# 05_LMS7002M_RF1.net
KiCad netlist of a schematic drawn in Altium Designer
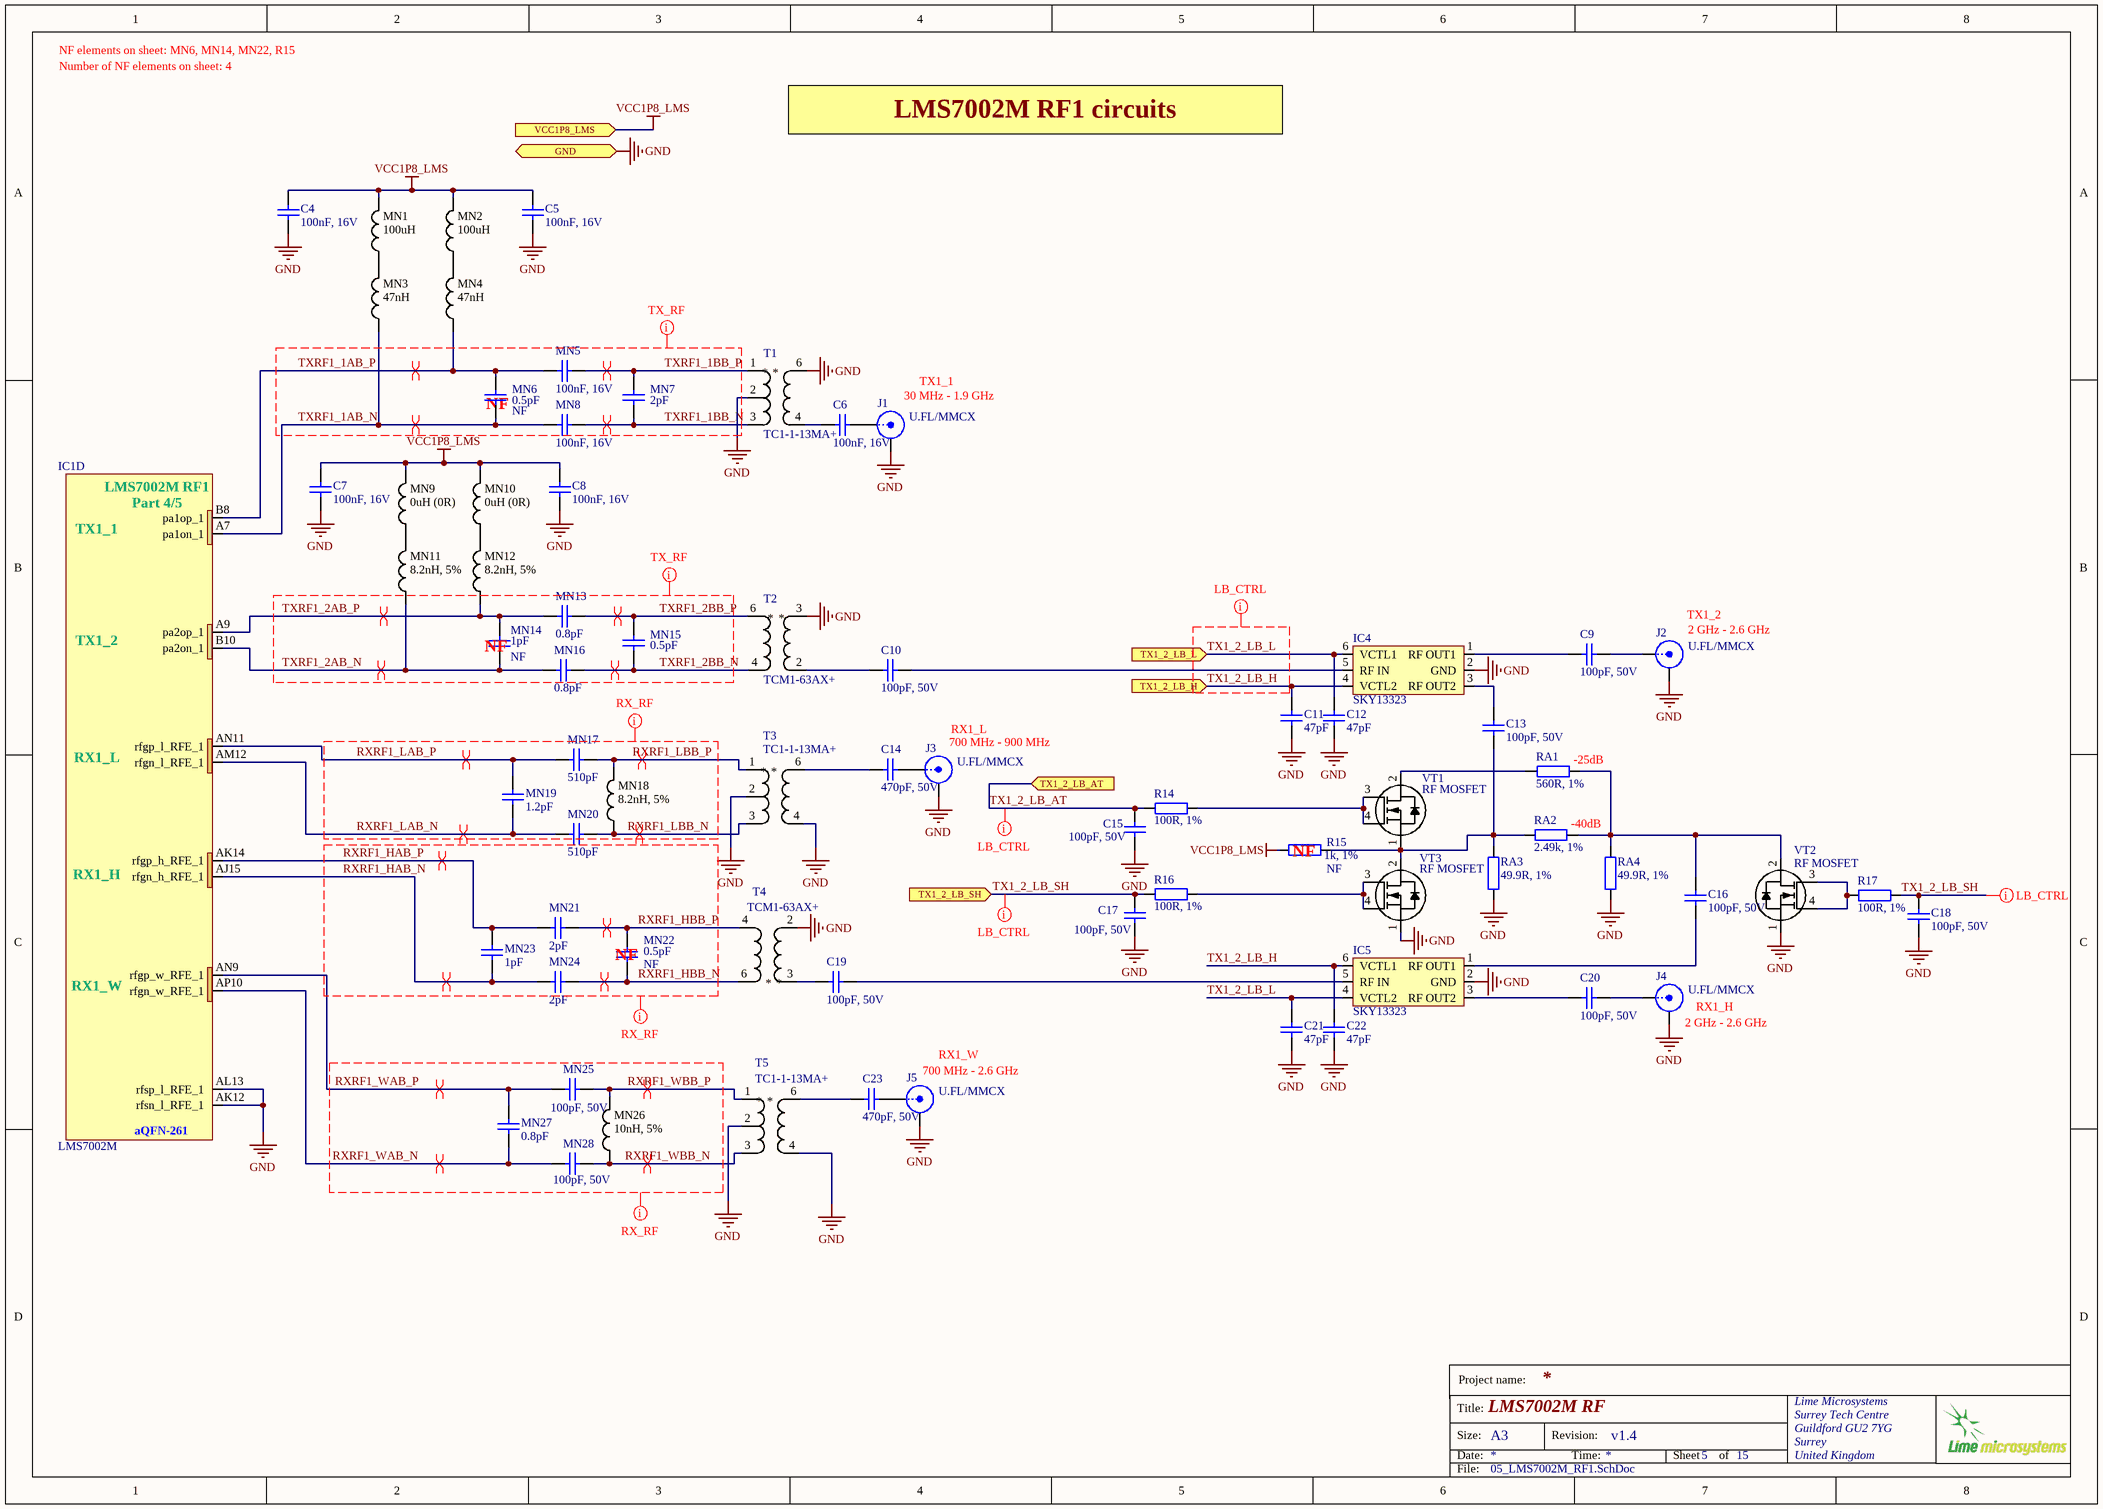
[diagram p0: 05_LMS7002M_RF1.SchDoc]

(export (version "E")
  (design (tool "Eeschema 10.0.6"))
  (components
    (comp (ref "C4")
      (value "100nF, 16V")
      (footprint "CAP0402")
      (fields
        (field (name "MANUFACTURER") "Murata Electronics")
        (field (name "TOLERANCE") "10 %")
        (field (name "MANUFACTURER PART NUMBER") "GRM155R71C104KA88D")
      )
      (libsource (lib "LimeMicroAltiumLib_schLib") (part "Cap_0402"))
    )
    (comp (ref "C5")
      (value "100nF, 16V")
      (footprint "CAP0402")
      (fields
        (field (name "MANUFACTURER") "Murata Electronics")
        (field (name "TOLERANCE") "10 %")
        (field (name "MANUFACTURER PART NUMBER") "GRM155R71C104KA88D")
      )
      (libsource (lib "LimeMicroAltiumLib_schLib") (part "Cap_0402"))
    )
    (comp (ref "C6")
      (value "100nF, 16V")
      (footprint "CAP0402")
      (fields
        (field (name "MANUFACTURER") "Murata Electronics")
        (field (name "TOLERANCE") "10 %")
        (field (name "MANUFACTURER PART NUMBER") "GRM155R71C104KA88D")
      )
      (libsource (lib "LimeMicroAltiumLib_schLib") (part "Cap_0402"))
    )
    (comp (ref "C7")
      (value "100nF, 16V")
      (footprint "CAP0402")
      (fields
        (field (name "MANUFACTURER") "Murata Electronics")
        (field (name "TOLERANCE") "10 %")
        (field (name "MANUFACTURER PART NUMBER") "GRM155R71C104KA88D")
      )
      (libsource (lib "LimeMicroAltiumLib_schLib") (part "Cap_0402"))
    )
    (comp (ref "C8")
      (value "100nF, 16V")
      (footprint "CAP0402")
      (fields
        (field (name "MANUFACTURER") "Murata Electronics")
        (field (name "TOLERANCE") "10 %")
        (field (name "MANUFACTURER PART NUMBER") "GRM155R71C104KA88D")
      )
      (libsource (lib "LimeMicroAltiumLib_schLib") (part "Cap_0402"))
    )
    (comp (ref "C9")
      (value "100pF, 50V")
      (footprint "CAP0402")
      (fields (field (name "TOLERANCE") "±5%") (field (name "MANUFACTURER") "Yageo"))
      (libsource (lib "LimeMicroAltiumLib_schLib") (part "Cap_0402"))
    )
    (comp (ref "C10")
      (value "100pF, 50V")
      (footprint "CAP0402")
      (fields (field (name "TOLERANCE") "±5%") (field (name "MANUFACTURER") "Yageo"))
      (libsource (lib "LimeMicroAltiumLib_schLib") (part "Cap_0402"))
    )
    (comp (ref "C11")
      (value "47pF")
      (footprint "CAP0402")
      (fields (field (name "TOLERANCE") "±1%") (field (name "MANUFACTURER") "TDK Corporation"))
      (libsource (lib "LimeMicroAltiumLib_schLib") (part "Cap_0402"))
    )
    (comp (ref "C12")
      (value "47pF")
      (footprint "CAP0402")
      (fields (field (name "TOLERANCE") "±1%") (field (name "MANUFACTURER") "TDK Corporation"))
      (libsource (lib "LimeMicroAltiumLib_schLib") (part "Cap_0402"))
    )
    (comp (ref "C13")
      (value "100pF, 50V")
      (footprint "CAP0402")
      (fields (field (name "TOLERANCE") "±5%") (field (name "MANUFACTURER") "Yageo"))
      (libsource (lib "LimeMicroAltiumLib_schLib") (part "Cap_0402"))
    )
    (comp (ref "C14")
      (value "470pF, 50V")
      (footprint "CAP0402")
      (fields
        (field (name "MANUFACTURER PART NUMBER") "C1005C0G1H471J050BA")
        (field (name "TOLERANCE") "±5%")
        (field (name "MANUFACTURER") "TDK Corporation")
      )
      (libsource (lib "LimeMicroAltiumLib_schLib") (part "Cap_0402"))
    )
    (comp (ref "C15")
      (value "100pF, 50V")
      (footprint "CAP0402")
      (fields (field (name "TOLERANCE") "±5%") (field (name "MANUFACTURER") "Yageo"))
      (libsource (lib "LimeMicroAltiumLib_schLib") (part "Cap_0402"))
    )
    (comp (ref "C16")
      (value "100pF, 50V")
      (footprint "CAP0402")
      (fields (field (name "TOLERANCE") "±5%") (field (name "MANUFACTURER") "Yageo"))
      (libsource (lib "LimeMicroAltiumLib_schLib") (part "Cap_0402"))
    )
    (comp (ref "C17")
      (value "100pF, 50V")
      (footprint "CAP0402")
      (fields (field (name "TOLERANCE") "±5%") (field (name "MANUFACTURER") "Yageo"))
      (libsource (lib "LimeMicroAltiumLib_schLib") (part "Cap_0402"))
    )
    (comp (ref "C18")
      (value "100pF, 50V")
      (footprint "CAP0402")
      (fields (field (name "TOLERANCE") "±5%") (field (name "MANUFACTURER") "Yageo"))
      (libsource (lib "LimeMicroAltiumLib_schLib") (part "Cap_0402"))
    )
    (comp (ref "C19")
      (value "100pF, 50V")
      (footprint "CAP0402")
      (fields (field (name "TOLERANCE") "±5%") (field (name "MANUFACTURER") "Yageo"))
      (libsource (lib "LimeMicroAltiumLib_schLib") (part "Cap_0402"))
    )
    (comp (ref "C20")
      (value "100pF, 50V")
      (footprint "CAP0402")
      (fields (field (name "TOLERANCE") "±5%") (field (name "MANUFACTURER") "Yageo"))
      (libsource (lib "LimeMicroAltiumLib_schLib") (part "Cap_0402"))
    )
    (comp (ref "C21")
      (value "47pF")
      (footprint "CAP0402")
      (fields (field (name "TOLERANCE") "±1%") (field (name "MANUFACTURER") "TDK Corporation"))
      (libsource (lib "LimeMicroAltiumLib_schLib") (part "Cap_0402"))
    )
    (comp (ref "C22")
      (value "47pF")
      (footprint "CAP0402")
      (fields (field (name "TOLERANCE") "±1%") (field (name "MANUFACTURER") "TDK Corporation"))
      (libsource (lib "LimeMicroAltiumLib_schLib") (part "Cap_0402"))
    )
    (comp (ref "C23")
      (value "470pF, 50V")
      (footprint "CAP0402")
      (fields
        (field (name "MANUFACTURER PART NUMBER") "C1005C0G1H471J050BA")
        (field (name "TOLERANCE") "±5%")
        (field (name "MANUFACTURER") "TDK Corporation")
      )
      (libsource (lib "LimeMicroAltiumLib_schLib") (part "Cap_0402"))
    )
    (comp (ref "IC1")
      (value "LMS7002M")
      (footprint "LMS7002M_v3")
      (fields (field (name "MANUFACTURER") "Lime Microsystems"))
      (libsource (lib "LimeMicroAltiumLib_schLib") (part "LMS7002M"))
    )
    (comp (ref "IC4")
      (value "SKY13323")
      (footprint "SKY13323-378LF")
      (description "SKY13323-378LF: 0.1-3.0 GHz GaAs SPDT Switch")
      (fields (field (name "MANUFACTURER") "Skyworks Solutions Inc."))
      (libsource (lib "LimeMicroAltiumLib_schLib") (part "SKY13323"))
    )
    (comp (ref "IC5")
      (value "SKY13323")
      (footprint "SKY13323-378LF")
      (description "SKY13323-378LF: 0.1-3.0 GHz GaAs SPDT Switch")
      (fields (field (name "MANUFACTURER") "Skyworks Solutions Inc."))
      (libsource (lib "LimeMicroAltiumLib_schLib") (part "SKY13323"))
    )
    (comp (ref "J1")
      (value "U.FL/MMCX")
      (footprint "MMCX_UFL_conn_u")
      (description "CONN UMC RCPT STR 50 OHM SMD")
      (fields (field (name "MANUFACTURER") "Molex, LLC"))
      (libsource (lib "LimeMicroAltiumLib_schLib") (part "RF_IF_connector"))
    )
    (comp (ref "J2")
      (value "U.FL/MMCX")
      (footprint "MMCX_UFL_conn_u")
      (description "CONN UMC RCPT STR 50 OHM SMD")
      (fields (field (name "MANUFACTURER") "Molex, LLC"))
      (libsource (lib "LimeMicroAltiumLib_schLib") (part "RF_IF_connector"))
    )
    (comp (ref "J3")
      (value "U.FL/MMCX")
      (footprint "MMCX_UFL_conn_u")
      (description "CONN UMC RCPT STR 50 OHM SMD")
      (fields (field (name "MANUFACTURER") "Molex, LLC"))
      (libsource (lib "LimeMicroAltiumLib_schLib") (part "RF_IF_connector"))
    )
    (comp (ref "J4")
      (value "U.FL/MMCX")
      (footprint "MMCX_UFL_conn_u")
      (description "CONN UMC RCPT STR 50 OHM SMD")
      (fields (field (name "MANUFACTURER") "Molex, LLC"))
      (libsource (lib "LimeMicroAltiumLib_schLib") (part "RF_IF_connector"))
    )
    (comp (ref "J5")
      (value "U.FL/MMCX")
      (footprint "MMCX_UFL_conn_u")
      (description "CONN UMC RCPT STR 50 OHM SMD")
      (fields (field (name "MANUFACTURER") "Molex, LLC"))
      (libsource (lib "LimeMicroAltiumLib_schLib") (part "RF_IF_connector"))
    )
    (comp (ref "MN1")
      (value "100uH")
      (footprint "RES0805")
      (fields
        (field (name "TOLERANCE") "±10%")
        (field (name "MANUFACTURER") "TDK Corporation")
        (field (name "MANUFACTURER PART NUMBER") "MLF2012C101KT000")
      )
      (libsource (lib "LimeMicroAltiumLib_schLib") (part "Inductor_0603"))
    )
    (comp (ref "MN2")
      (value "100uH")
      (footprint "RES0805")
      (fields
        (field (name "TOLERANCE") "±10%")
        (field (name "MANUFACTURER") "TDK Corporation")
        (field (name "MANUFACTURER PART NUMBER") "MLF2012C101KT000")
      )
      (libsource (lib "LimeMicroAltiumLib_schLib") (part "Inductor_0603"))
    )
    (comp (ref "MN3")
      (value "47nH")
      (footprint "RES0402")
      (fields
        (field (name "MANUFACTURER") "COILCRAFT")
        (field (name "MANUFACTURER PART NUMBER") "0402HP-47NXJLU")
      )
      (libsource (lib "LimeMicroAltiumLib_schLib") (part "Inductor_0603"))
    )
    (comp (ref "MN4")
      (value "47nH")
      (footprint "RES0402")
      (fields
        (field (name "MANUFACTURER") "COILCRAFT")
        (field (name "MANUFACTURER PART NUMBER") "0402HP-47NXJLU")
      )
      (libsource (lib "LimeMicroAltiumLib_schLib") (part "Inductor_0603"))
    )
    (comp (ref "MN5")
      (value "100nF, 16V")
      (footprint "CAP0402")
      (fields
        (field (name "MANUFACTURER") "Murata Electronics")
        (field (name "TOLERANCE") "10 %")
        (field (name "MANUFACTURER PART NUMBER") "GRM155R71C104KA88D")
      )
      (libsource (lib "LimeMicroAltiumLib_schLib") (part "Cap_0402"))
    )
    (comp (ref "MN6")
      (value "0.5pF")
      (footprint "CAP0402")
      (fields
        (field (name "ASSEMBLY INFO") "NF")
        (field (name "TOLERANCE") "±0.25pF")
        (field (name "MANUFACTURER") "Yageo")
      )
      (libsource (lib "LimeMicroAltiumLib_schLib") (part "Cap_0402"))
    )
    (comp (ref "MN7")
      (value "2pF")
      (footprint "CAP0402")
      (fields (field (name "MANUFACTURER PART NUMBER") "04025U2R0BAT2A") (field (name "MANUFACTURER") "AVX"))
      (libsource (lib "LimeMicroAltiumLib_schLib") (part "Cap_0402"))
    )
    (comp (ref "MN8")
      (value "100nF, 16V")
      (footprint "CAP0402")
      (fields
        (field (name "MANUFACTURER") "Murata Electronics")
        (field (name "TOLERANCE") "10 %")
        (field (name "MANUFACTURER PART NUMBER") "GRM155R71C104KA88D")
      )
      (libsource (lib "LimeMicroAltiumLib_schLib") (part "Cap_0402"))
    )
    (comp (ref "MN9")
      (value "0uH (0R)")
      (footprint "RES0805")
      (fields (field (name "MANUFACTURER") "BOURNS"))
      (libsource (lib "LimeMicroAltiumLib_schLib") (part "Inductor_0603"))
    )
    (comp (ref "MN10")
      (value "0uH (0R)")
      (footprint "RES0805")
      (fields (field (name "MANUFACTURER") "BOURNS"))
      (libsource (lib "LimeMicroAltiumLib_schLib") (part "Inductor_0603"))
    )
    (comp (ref "MN11")
      (value "8.2nH, 5%")
      (footprint "RES0402")
      (fields (field (name "MANUFACTURER") "COILCRAFT"))
      (libsource (lib "LimeMicroAltiumLib_schLib") (part "Inductor_0603"))
    )
    (comp (ref "MN12")
      (value "8.2nH, 5%")
      (footprint "RES0402")
      (fields (field (name "MANUFACTURER") "COILCRAFT"))
      (libsource (lib "LimeMicroAltiumLib_schLib") (part "Inductor_0603"))
    )
    (comp (ref "MN13")
      (value "0.8pF")
      (footprint "CAP0402")
      (fields
        (field (name "TOLERANCE") "±0.1pF")
        (field (name "MANUFACTURER") "Murata Electronics North America")
        (field (name "MANUFACTURER PART NUMBER") "GRM1555C1HR80BA01D")
      )
      (libsource (lib "LimeMicroAltiumLib_schLib") (part "Cap_0402"))
    )
    (comp (ref "MN14")
      (value "1pF")
      (footprint "CAP0402")
      (fields
        (field (name "ASSEMBLY INFO") "NF")
        (field (name "MANUFACTURER") "TDK Corporation")
        (field (name "TOLERANCE") "±0.1pF")
      )
      (libsource (lib "LimeMicroAltiumLib_schLib") (part "Cap_0402"))
    )
    (comp (ref "MN15")
      (value "0.5pF")
      (footprint "CAP0402")
      (fields (field (name "TOLERANCE") "±0.25pF") (field (name "MANUFACTURER") "Yageo"))
      (libsource (lib "LimeMicroAltiumLib_schLib") (part "Cap_0402"))
    )
    (comp (ref "MN16")
      (value "0.8pF")
      (footprint "CAP0402")
      (fields
        (field (name "TOLERANCE") "±0.1pF")
        (field (name "MANUFACTURER") "Murata Electronics North America")
        (field (name "MANUFACTURER PART NUMBER") "GRM1555C1HR80BA01D")
      )
      (libsource (lib "LimeMicroAltiumLib_schLib") (part "Cap_0402"))
    )
    (comp (ref "MN17")
      (value "510pF")
      (footprint "CAP0402")
      (fields
        (field (name "TOLERANCE") "±5%")
        (field (name "MANUFACTURER") "Murata Electronics North America")
        (field (name "MANUFACTURER PART NUMBER") "GRM1555C1H511JA01D")
      )
      (libsource (lib "LimeMicroAltiumLib_schLib") (part "Cap_0402"))
    )
    (comp (ref "MN18")
      (value "8.2nH, 5%")
      (footprint "RES0402")
      (fields (field (name "MANUFACTURER") "COILCRAFT"))
      (libsource (lib "LimeMicroAltiumLib_schLib") (part "Inductor_0603"))
    )
    (comp (ref "MN19")
      (value "1.2pF")
      (footprint "CAP0402")
      (fields
        (field (name "MANUFACTURER") "Murata Electronics North America")
        (field (name "MANUFACTURER PART NUMBER") "GRM1555C1H1R2CA01D")
        (field (name "TOLERANCE") "±0.25pF")
      )
      (libsource (lib "LimeMicroAltiumLib_schLib") (part "Cap_0402"))
    )
    (comp (ref "MN20")
      (value "510pF")
      (footprint "CAP0402")
      (fields
        (field (name "TOLERANCE") "±5%")
        (field (name "MANUFACTURER") "Murata Electronics North America")
        (field (name "MANUFACTURER PART NUMBER") "GRM1555C1H511JA01D")
      )
      (libsource (lib "LimeMicroAltiumLib_schLib") (part "Cap_0402"))
    )
    (comp (ref "MN21")
      (value "2pF")
      (footprint "CAP0402")
      (fields (field (name "MANUFACTURER PART NUMBER") "04025U2R0BAT2A") (field (name "MANUFACTURER") "AVX"))
      (libsource (lib "LimeMicroAltiumLib_schLib") (part "Cap_0402"))
    )
    (comp (ref "MN22")
      (value "0.5pF")
      (footprint "CAP0402")
      (fields
        (field (name "ASSEMBLY INFO") "NF")
        (field (name "TOLERANCE") "±0.25pF")
        (field (name "MANUFACTURER") "Yageo")
      )
      (libsource (lib "LimeMicroAltiumLib_schLib") (part "Cap_0402"))
    )
    (comp (ref "MN23")
      (value "1pF")
      (footprint "CAP0402")
      (fields (field (name "MANUFACTURER") "TDK Corporation") (field (name "TOLERANCE") "±0.1pF"))
      (libsource (lib "LimeMicroAltiumLib_schLib") (part "Cap_0402"))
    )
    (comp (ref "MN24")
      (value "2pF")
      (footprint "CAP0402")
      (fields (field (name "MANUFACTURER PART NUMBER") "04025U2R0BAT2A") (field (name "MANUFACTURER") "AVX"))
      (libsource (lib "LimeMicroAltiumLib_schLib") (part "Cap_0402"))
    )
    (comp (ref "MN25")
      (value "100pF, 50V")
      (footprint "CAP0402")
      (fields (field (name "TOLERANCE") "±5%") (field (name "MANUFACTURER") "Yageo"))
      (libsource (lib "LimeMicroAltiumLib_schLib") (part "Cap_0402"))
    )
    (comp (ref "MN26")
      (value "10nH, 5%")
      (footprint "RES0402")
      (fields (field (name "MANUFACTURER") "COILCRAFT"))
      (libsource (lib "LimeMicroAltiumLib_schLib") (part "Inductor_0603"))
    )
    (comp (ref "MN27")
      (value "0.8pF")
      (footprint "CAP0402")
      (fields
        (field (name "TOLERANCE") "±0.1pF")
        (field (name "MANUFACTURER") "Murata Electronics North America")
        (field (name "MANUFACTURER PART NUMBER") "GRM1555C1HR80BA01D")
      )
      (libsource (lib "LimeMicroAltiumLib_schLib") (part "Cap_0402"))
    )
    (comp (ref "MN28")
      (value "100pF, 50V")
      (footprint "CAP0402")
      (fields (field (name "TOLERANCE") "±5%") (field (name "MANUFACTURER") "Yageo"))
      (libsource (lib "LimeMicroAltiumLib_schLib") (part "Cap_0402"))
    )
    (comp (ref "R14")
      (value "100R, 1%")
      (footprint "RES0402")
      (fields (field (name "TOLERANCE") "±1%") (field (name "MANUFACTURER") "Stackpole Electronics Inc."))
      (libsource (lib "LimeFPGAboard_schLib") (part "Res_0402"))
    )
    (comp (ref "R15")
      (value "1k, 1%")
      (footprint "RES0402")
      (fields
        (field (name "ASSEMBLY INFO") "NF")
        (field (name "MANUFACTURER") "Stackpole Electronics Inc")
        (field (name "TOLERANCE") "±1%")
      )
      (libsource (lib "LimeMicroAltiumLib_schLib") (part "Res_0402"))
    )
    (comp (ref "R16")
      (value "100R, 1%")
      (footprint "RES0402")
      (fields (field (name "TOLERANCE") "±1%") (field (name "MANUFACTURER") "Stackpole Electronics Inc."))
      (libsource (lib "LimeFPGAboard_schLib") (part "Res_0402"))
    )
    (comp (ref "R17")
      (value "100R, 1%")
      (footprint "RES0402")
      (fields (field (name "TOLERANCE") "±1%") (field (name "MANUFACTURER") "Stackpole Electronics Inc."))
      (libsource (lib "LimeFPGAboard_schLib") (part "Res_0402"))
    )
    (comp (ref "RA1")
      (value "560R, 1%")
      (footprint "RES0402")
      (fields
        (field (name "MANUFACTURER PART NUMBER") "CRCW0402560RFKED")
        (field (name "TOLERANCE") "±1%")
        (field (name "MANUFACTURER") "Vishay Dale")
      )
      (libsource (lib "LimeMicroAltiumLib_schLib") (part "Res_0402"))
    )
    (comp (ref "RA2")
      (value "2.49k, 1%")
      (footprint "RES0402")
      (fields
        (field (name "TOLERANCE") "±1%")
        (field (name "MANUFACTURER PART NUMBER") "RC0402FR-072K49L")
        (field (name "MANUFACTURER") "Yageo")
      )
      (libsource (lib "LimeMicroAltiumLib_schLib") (part "Res_0402"))
    )
    (comp (ref "RA3")
      (value "49.9R, 1%")
      (footprint "RES0402")
      (fields
        (field (name "TOLERANCE") "±1%")
        (field (name "MANUFACTURER") "Samsung Electro-Mechanics America, Inc.")
        (field (name "MANUFACTURER PART NUMBER") "RC1005F49R9CS")
      )
      (libsource (lib "LimeMicroAltiumLib_schLib") (part "Res_0402"))
    )
    (comp (ref "RA4")
      (value "49.9R, 1%")
      (footprint "RES0402")
      (fields
        (field (name "TOLERANCE") "±1%")
        (field (name "MANUFACTURER") "Samsung Electro-Mechanics America, Inc.")
        (field (name "MANUFACTURER PART NUMBER") "RC1005F49R9CS")
      )
      (libsource (lib "LimeMicroAltiumLib_schLib") (part "Res_0402"))
    )
    (comp (ref "T1")
      (value "TC1-1-13MA+")
      (footprint "TC1-1-13MA+_v2")
      (fields (field (name "MANUFACTURER") "Mini-Circuits"))
      (libsource (lib "LimeMicroAltiumLib_schLib") (part "Balun"))
    )
    (comp (ref "T2")
      (value "TCM1-63AX+")
      (footprint "TCM1-63AX+_v2")
      (fields (field (name "MANUFACTURER") "Mini-circuits"))
      (libsource (lib "") (part "Balun_v2_1"))
    )
    (comp (ref "T3")
      (value "TC1-1-13MA+")
      (footprint "TC1-1-13MA+_v2")
      (fields (field (name "MANUFACTURER") "Mini-Circuits"))
      (libsource (lib "LimeMicroAltiumLib_schLib") (part "Balun"))
    )
    (comp (ref "T4")
      (value "TCM1-63AX+")
      (footprint "TCM1-63AX+_v2")
      (fields (field (name "MANUFACTURER") "Mini-circuits"))
      (libsource (lib "LimeMicroAltiumLib_schLib") (part "Balun_v2"))
    )
    (comp (ref "T5")
      (value "TC1-1-13MA+")
      (footprint "TC1-1-13MA+_v2")
      (fields (field (name "MANUFACTURER") "Mini-Circuits"))
      (libsource (lib "LimeMicroAltiumLib_schLib") (part "Balun"))
    )
    (comp (ref "VT1")
      (value "RF MOSFET")
      (footprint "BF1105R_SOT143R4")
      (fields (field (name "MANUFACTURER") "NXP Semiconductors"))
      (libsource (lib "LimeMicroAltiumLib_schLib") (part "BF1105R,215"))
    )
    (comp (ref "VT2")
      (value "RF MOSFET")
      (footprint "BF1105R_SOT143R4")
      (fields (field (name "MANUFACTURER") "NXP Semiconductors"))
      (libsource (lib "LimeMicroAltiumLib_schLib") (part "BF1105R,215"))
    )
    (comp (ref "VT3")
      (value "RF MOSFET")
      (footprint "BF1105R_SOT143R4")
      (fields (field (name "MANUFACTURER") "NXP Semiconductors"))
      (libsource (lib "LimeMicroAltiumLib_schLib") (part "BF1105R,215"))
    )
  )
  (nets
    (net (code "1") (name "/RXRF1_HAB_N") (class "Default")
      (node (ref "IC1") (pin "AJ15") (pinfunction "rfgn_h_RFE_1_AJ15") (pintype "passive"))
      (node (ref "MN23") (pin "1") (pinfunction "1_1") (pintype "passive"))
      (node (ref "MN24") (pin "2") (pinfunction "2_2") (pintype "passive"))
    )
    (net (code "2") (name "/RXRF1_HAB_P") (class "Default")
      (node (ref "IC1") (pin "AK14") (pinfunction "rfgp_h_RFE_1_AK14") (pintype "passive"))
      (node (ref "MN21") (pin "2") (pinfunction "2_2") (pintype "passive"))
      (node (ref "MN23") (pin "2") (pinfunction "2_2") (pintype "passive"))
    )
    (net (code "3") (name "/RXRF1_HBB_N") (class "Default")
      (node (ref "MN22") (pin "1") (pinfunction "1_1") (pintype "passive"))
      (node (ref "MN24") (pin "1") (pinfunction "1_1") (pintype "passive"))
      (node (ref "T4") (pin "6") (pinfunction "6_6") (pintype "passive"))
    )
    (net (code "4") (name "/RXRF1_HBB_P") (class "Default")
      (node (ref "MN21") (pin "1") (pinfunction "1_1") (pintype "passive"))
      (node (ref "MN22") (pin "2") (pinfunction "2_2") (pintype "passive"))
      (node (ref "T4") (pin "4") (pinfunction "4_4") (pintype "passive"))
    )
    (net (code "5") (name "/RXRF1_LAB_N") (class "Default")
      (node (ref "IC1") (pin "AM12") (pinfunction "rfgn_l_RFE_1_AM12") (pintype "passive"))
      (node (ref "MN19") (pin "1") (pinfunction "1_1") (pintype "passive"))
      (node (ref "MN20") (pin "2") (pinfunction "2_2") (pintype "passive"))
    )
    (net (code "6") (name "/RXRF1_LAB_P") (class "Default")
      (node (ref "IC1") (pin "AN11") (pinfunction "rfgp_l_RFE_1_AN11") (pintype "passive"))
      (node (ref "MN17") (pin "2") (pinfunction "2_2") (pintype "passive"))
      (node (ref "MN19") (pin "2") (pinfunction "2_2") (pintype "passive"))
    )
    (net (code "7") (name "/RXRF1_LBB_N") (class "Default")
      (node (ref "MN18") (pin "1") (pinfunction "1_1") (pintype "passive"))
      (node (ref "MN20") (pin "1") (pinfunction "1_1") (pintype "passive"))
      (node (ref "T3") (pin "3") (pinfunction "3_3") (pintype "passive"))
    )
    (net (code "8") (name "/RXRF1_LBB_P") (class "Default")
      (node (ref "MN17") (pin "1") (pinfunction "1_1") (pintype "passive"))
      (node (ref "MN18") (pin "2") (pinfunction "2_2") (pintype "passive"))
      (node (ref "T3") (pin "1") (pinfunction "1_1") (pintype "passive"))
    )
    (net (code "9") (name "/RXRF1_WAB_N") (class "Default")
      (node (ref "IC1") (pin "AP10") (pinfunction "rfgn_w_RFE_1_AP10") (pintype "passive"))
      (node (ref "MN27") (pin "2") (pinfunction "2_2") (pintype "passive"))
      (node (ref "MN28") (pin "2") (pinfunction "2_2") (pintype "passive"))
    )
    (net (code "10") (name "/RXRF1_WAB_P") (class "Default")
      (node (ref "IC1") (pin "AN9") (pinfunction "rfgp_w_RFE_1_AN9") (pintype "passive"))
      (node (ref "MN25") (pin "2") (pinfunction "2_2") (pintype "passive"))
      (node (ref "MN27") (pin "1") (pinfunction "1_1") (pintype "passive"))
    )
    (net (code "11") (name "/RXRF1_WBB_N") (class "Default")
      (node (ref "MN26") (pin "1") (pinfunction "1_1") (pintype "passive"))
      (node (ref "MN28") (pin "1") (pinfunction "1_1") (pintype "passive"))
      (node (ref "T5") (pin "3") (pinfunction "3_3") (pintype "passive"))
    )
    (net (code "12") (name "/RXRF1_WBB_P") (class "Default")
      (node (ref "MN25") (pin "1") (pinfunction "1_1") (pintype "passive"))
      (node (ref "MN26") (pin "2") (pinfunction "2_2") (pintype "passive"))
      (node (ref "T5") (pin "1") (pinfunction "1_1") (pintype "passive"))
    )
    (net (code "13") (name "/TX1_2_LB_AT") (class "Default")
      (node (ref "C15") (pin "1") (pinfunction "1_1") (pintype "passive"))
      (node (ref "R14") (pin "2") (pinfunction "2_2") (pintype "passive"))
    )
    (net (code "14") (name "/TX1_2_LB_H") (class "Default")
      (node (ref "C11") (pin "2") (pinfunction "2_2") (pintype "passive"))
      (node (ref "C22") (pin "2") (pinfunction "2_2") (pintype "passive"))
      (node (ref "IC4") (pin "4") (pinfunction "VCTL2_4") (pintype "input"))
      (node (ref "IC5") (pin "6") (pinfunction "VCTL1_6") (pintype "input"))
    )
    (net (code "15") (name "/TX1_2_LB_L") (class "Default")
      (node (ref "C12") (pin "2") (pinfunction "2_2") (pintype "passive"))
      (node (ref "C21") (pin "2") (pinfunction "2_2") (pintype "passive"))
      (node (ref "IC4") (pin "6") (pinfunction "VCTL1_6") (pintype "input"))
      (node (ref "IC5") (pin "4") (pinfunction "VCTL2_4") (pintype "input"))
    )
    (net (code "16") (name "/TX1_2_LB_SH") (class "Default")
      (node (ref "C17") (pin "1") (pinfunction "1_1") (pintype "passive"))
      (node (ref "C18") (pin "1") (pinfunction "1_1") (pintype "passive"))
      (node (ref "R16") (pin "2") (pinfunction "2_2") (pintype "passive"))
      (node (ref "R17") (pin "1") (pinfunction "1_1") (pintype "passive"))
    )
    (net (code "17") (name "/TXRF1_1AB_N") (class "Default")
      (node (ref "IC1") (pin "A7") (pinfunction "pa1on_1_A7") (pintype "passive"))
      (node (ref "MN3") (pin "1") (pinfunction "1_1") (pintype "passive"))
      (node (ref "MN6") (pin "1") (pinfunction "1_1") (pintype "passive"))
      (node (ref "MN8") (pin "1") (pinfunction "1_1") (pintype "passive"))
    )
    (net (code "18") (name "/TXRF1_1AB_P") (class "Default")
      (node (ref "IC1") (pin "B8") (pinfunction "pa1op_1_B8") (pintype "passive"))
      (node (ref "MN4") (pin "1") (pinfunction "1_1") (pintype "passive"))
      (node (ref "MN5") (pin "2") (pinfunction "2_2") (pintype "passive"))
      (node (ref "MN6") (pin "2") (pinfunction "2_2") (pintype "passive"))
    )
    (net (code "19") (name "/TXRF1_1BB_N") (class "Default")
      (node (ref "MN7") (pin "1") (pinfunction "1_1") (pintype "passive"))
      (node (ref "MN8") (pin "2") (pinfunction "2_2") (pintype "passive"))
      (node (ref "T1") (pin "3") (pinfunction "3_3") (pintype "passive"))
    )
    (net (code "20") (name "/TXRF1_1BB_P") (class "Default")
      (node (ref "MN5") (pin "1") (pinfunction "1_1") (pintype "passive"))
      (node (ref "MN7") (pin "2") (pinfunction "2_2") (pintype "passive"))
      (node (ref "T1") (pin "1") (pinfunction "1_1") (pintype "passive"))
    )
    (net (code "21") (name "/TXRF1_2AB_N") (class "Default")
      (node (ref "IC1") (pin "B10") (pinfunction "pa2on_1_B10") (pintype "passive"))
      (node (ref "MN11") (pin "1") (pinfunction "1_1") (pintype "passive"))
      (node (ref "MN14") (pin "2") (pinfunction "2_2") (pintype "passive"))
      (node (ref "MN16") (pin "2") (pinfunction "2_2") (pintype "passive"))
    )
    (net (code "22") (name "/TXRF1_2AB_P") (class "Default")
      (node (ref "IC1") (pin "A9") (pinfunction "pa2op_1_A9") (pintype "passive"))
      (node (ref "MN12") (pin "1") (pinfunction "1_1") (pintype "passive"))
      (node (ref "MN13") (pin "2") (pinfunction "2_2") (pintype "passive"))
      (node (ref "MN14") (pin "1") (pinfunction "1_1") (pintype "passive"))
    )
    (net (code "23") (name "/TXRF1_2BB_N") (class "Default")
      (node (ref "MN15") (pin "1") (pinfunction "1_1") (pintype "passive"))
      (node (ref "MN16") (pin "1") (pinfunction "1_1") (pintype "passive"))
      (node (ref "T2") (pin "4") (pinfunction "4_4") (pintype "passive"))
    )
    (net (code "24") (name "/TXRF1_2BB_P") (class "Default")
      (node (ref "MN13") (pin "1") (pinfunction "1_1") (pintype "passive"))
      (node (ref "MN15") (pin "2") (pinfunction "2_2") (pintype "passive"))
      (node (ref "T2") (pin "6") (pinfunction "6_6") (pintype "passive"))
    )
    (net (code "25") (name "GND") (class "Default")
      (node (ref "C11") (pin "1") (pinfunction "1_1") (pintype "passive"))
      (node (ref "C12") (pin "1") (pinfunction "1_1") (pintype "passive"))
      (node (ref "C15") (pin "2") (pinfunction "2_2") (pintype "passive"))
      (node (ref "C17") (pin "2") (pinfunction "2_2") (pintype "passive"))
      (node (ref "C18") (pin "2") (pinfunction "2_2") (pintype "passive"))
      (node (ref "C21") (pin "1") (pinfunction "1_1") (pintype "passive"))
      (node (ref "C22") (pin "1") (pinfunction "1_1") (pintype "passive"))
      (node (ref "C4") (pin "1") (pinfunction "1_1") (pintype "passive"))
      (node (ref "C5") (pin "1") (pinfunction "1_1") (pintype "passive"))
      (node (ref "C7") (pin "1") (pinfunction "1_1") (pintype "passive"))
      (node (ref "C8") (pin "1") (pinfunction "1_1") (pintype "passive"))
      (node (ref "IC1") (pin "AK12") (pinfunction "rfsn_l_RFE_1_AK12") (pintype "passive"))
      (node (ref "IC1") (pin "AL13") (pinfunction "rfsp_l_RFE_1_AL13") (pintype "passive"))
      (node (ref "IC4") (pin "2") (pinfunction "GND_2") (pintype "passive"))
      (node (ref "IC5") (pin "2") (pinfunction "GND_2") (pintype "passive"))
      (node (ref "J1") (pin "2") (pinfunction "Y_2") (pintype "passive"))
      (node (ref "J2") (pin "2") (pinfunction "Y_2") (pintype "passive"))
      (node (ref "J3") (pin "2") (pinfunction "Y_2") (pintype "passive"))
      (node (ref "J4") (pin "2") (pinfunction "Y_2") (pintype "passive"))
      (node (ref "J5") (pin "2") (pinfunction "Y_2") (pintype "passive"))
      (node (ref "RA3") (pin "1") (pinfunction "1_1") (pintype "passive"))
      (node (ref "RA4") (pin "1") (pinfunction "1_1") (pintype "passive"))
      (node (ref "T1") (pin "2") (pinfunction "2_2") (pintype "passive"))
      (node (ref "T1") (pin "6") (pinfunction "6_6") (pintype "passive"))
      (node (ref "T2") (pin "3") (pinfunction "3_3") (pintype "passive"))
      (node (ref "T3") (pin "2") (pinfunction "2_2") (pintype "passive"))
      (node (ref "T3") (pin "4") (pinfunction "4_4") (pintype "passive"))
      (node (ref "T4") (pin "2") (pinfunction "2_2") (pintype "passive"))
      (node (ref "T5") (pin "2") (pinfunction "2_2") (pintype "passive"))
      (node (ref "T5") (pin "4") (pinfunction "4_4") (pintype "passive"))
      (node (ref "VT2") (pin "1") (pinfunction "S_1") (pintype "passive"))
      (node (ref "VT3") (pin "1") (pinfunction "S_1") (pintype "passive"))
    )
    (net (code "26") (name "Net-(C6-Pad2)") (class "Default")
      (node (ref "C6") (pin "2") (pinfunction "2_2") (pintype "passive"))
      (node (ref "T1") (pin "4") (pinfunction "4_4") (pintype "passive"))
    )
    (net (code "27") (name "Net-(C10-Pad2)") (class "Default")
      (node (ref "C10") (pin "2") (pinfunction "2_2") (pintype "passive"))
      (node (ref "T2") (pin "2") (pinfunction "2_2") (pintype "passive"))
    )
    (net (code "28") (name "Net-(C14-Pad2)") (class "Default")
      (node (ref "C14") (pin "2") (pinfunction "2_2") (pintype "passive"))
      (node (ref "T3") (pin "6") (pinfunction "6_6") (pintype "passive"))
    )
    (net (code "29") (name "Net-(C19-Pad2)") (class "Default")
      (node (ref "C19") (pin "2") (pinfunction "2_2") (pintype "passive"))
      (node (ref "T4") (pin "3") (pinfunction "3_3") (pintype "passive"))
    )
    (net (code "30") (name "Net-(C23-Pad2)") (class "Default")
      (node (ref "C23") (pin "2") (pinfunction "2_2") (pintype "passive"))
      (node (ref "T5") (pin "6") (pinfunction "6_6") (pintype "passive"))
    )
    (net (code "31") (name "Net-(IC4-RF_IN)") (class "Default")
      (node (ref "C10") (pin "1") (pinfunction "1_1") (pintype "passive"))
      (node (ref "IC4") (pin "5") (pinfunction "RF_IN_5") (pintype "input"))
    )
    (net (code "32") (name "Net-(IC4-RF_OUT1)") (class "Default")
      (node (ref "C9") (pin "2") (pinfunction "2_2") (pintype "passive"))
      (node (ref "IC4") (pin "1") (pinfunction "RF_OUT1_1") (pintype "output"))
    )
    (net (code "33") (name "Net-(IC4-RF_OUT2)") (class "Default")
      (node (ref "C13") (pin "1") (pinfunction "1_1") (pintype "passive"))
      (node (ref "IC4") (pin "3") (pinfunction "RF_OUT2_3") (pintype "output"))
    )
    (net (code "34") (name "Net-(IC5-RF_IN)") (class "Default")
      (node (ref "C19") (pin "1") (pinfunction "1_1") (pintype "passive"))
      (node (ref "IC5") (pin "5") (pinfunction "RF_IN_5") (pintype "input"))
    )
    (net (code "35") (name "Net-(IC5-RF_OUT1)") (class "Default")
      (node (ref "C16") (pin "2") (pinfunction "2_2") (pintype "passive"))
      (node (ref "IC5") (pin "1") (pinfunction "RF_OUT1_1") (pintype "output"))
    )
    (net (code "36") (name "Net-(IC5-RF_OUT2)") (class "Default")
      (node (ref "C20") (pin "2") (pinfunction "2_2") (pintype "passive"))
      (node (ref "IC5") (pin "3") (pinfunction "RF_OUT2_3") (pintype "output"))
    )
    (net (code "37") (name "Net-(J1-X)") (class "Default")
      (node (ref "C6") (pin "1") (pinfunction "1_1") (pintype "passive"))
      (node (ref "J1") (pin "1") (pinfunction "X_1") (pintype "passive"))
    )
    (net (code "38") (name "Net-(J2-X)") (class "Default")
      (node (ref "C9") (pin "1") (pinfunction "1_1") (pintype "passive"))
      (node (ref "J2") (pin "1") (pinfunction "X_1") (pintype "passive"))
    )
    (net (code "39") (name "Net-(J3-X)") (class "Default")
      (node (ref "C14") (pin "1") (pinfunction "1_1") (pintype "passive"))
      (node (ref "J3") (pin "1") (pinfunction "X_1") (pintype "passive"))
    )
    (net (code "40") (name "Net-(J4-X)") (class "Default")
      (node (ref "C20") (pin "1") (pinfunction "1_1") (pintype "passive"))
      (node (ref "J4") (pin "1") (pinfunction "X_1") (pintype "passive"))
    )
    (net (code "41") (name "Net-(J5-X)") (class "Default")
      (node (ref "C23") (pin "1") (pinfunction "1_1") (pintype "passive"))
      (node (ref "J5") (pin "1") (pinfunction "X_1") (pintype "passive"))
    )
    (net (code "42") (name "Net-(MN1-Pad1)") (class "Default")
      (node (ref "MN1") (pin "1") (pinfunction "1_1") (pintype "passive"))
      (node (ref "MN3") (pin "2") (pinfunction "2_2") (pintype "passive"))
    )
    (net (code "43") (name "Net-(MN2-Pad1)") (class "Default")
      (node (ref "MN2") (pin "1") (pinfunction "1_1") (pintype "passive"))
      (node (ref "MN4") (pin "2") (pinfunction "2_2") (pintype "passive"))
    )
    (net (code "44") (name "Net-(MN10-Pad1)") (class "Default")
      (node (ref "MN10") (pin "1") (pinfunction "1_1") (pintype "passive"))
      (node (ref "MN12") (pin "2") (pinfunction "2_2") (pintype "passive"))
    )
    (net (code "45") (name "Net-(MN11-Pad2)") (class "Default")
      (node (ref "MN11") (pin "2") (pinfunction "2_2") (pintype "passive"))
      (node (ref "MN9") (pin "1") (pinfunction "1_1") (pintype "passive"))
    )
    (net (code "46") (name "Net-(VT1-D)") (class "Default")
      (node (ref "RA1") (pin "2") (pinfunction "2_2") (pintype "passive"))
      (node (ref "VT1") (pin "2") (pinfunction "D_2") (pintype "passive"))
    )
    (net (code "47") (name "Net-(VT1-G1)") (class "Default")
      (node (ref "R14") (pin "1") (pinfunction "1_1") (pintype "passive"))
      (node (ref "VT1") (pin "3") (pinfunction "G2_3") (pintype "passive"))
      (node (ref "VT1") (pin "4") (pinfunction "G1_4") (pintype "passive"))
    )
    (net (code "48") (name "Net-(VT1-S)") (class "Default")
      (node (ref "C13") (pin "2") (pinfunction "2_2") (pintype "passive"))
      (node (ref "R15") (pin "1") (pinfunction "1_1") (pintype "passive"))
      (node (ref "RA2") (pin "1") (pinfunction "1_1") (pintype "passive"))
      (node (ref "RA3") (pin "2") (pinfunction "2_2") (pintype "passive"))
      (node (ref "VT1") (pin "1") (pinfunction "S_1") (pintype "passive"))
      (node (ref "VT3") (pin "2") (pinfunction "D_2") (pintype "passive"))
    )
    (net (code "49") (name "Net-(VT2-D)") (class "Default")
      (node (ref "C16") (pin "1") (pinfunction "1_1") (pintype "passive"))
      (node (ref "RA1") (pin "1") (pinfunction "1_1") (pintype "passive"))
      (node (ref "RA2") (pin "2") (pinfunction "2_2") (pintype "passive"))
      (node (ref "RA4") (pin "2") (pinfunction "2_2") (pintype "passive"))
      (node (ref "VT2") (pin "2") (pinfunction "D_2") (pintype "passive"))
    )
    (net (code "50") (name "Net-(VT2-G1)") (class "Default")
      (node (ref "R17") (pin "2") (pinfunction "2_2") (pintype "passive"))
      (node (ref "VT2") (pin "3") (pinfunction "G2_3") (pintype "passive"))
      (node (ref "VT2") (pin "4") (pinfunction "G1_4") (pintype "passive"))
    )
    (net (code "51") (name "Net-(VT3-G1)") (class "Default")
      (node (ref "R16") (pin "1") (pinfunction "1_1") (pintype "passive"))
      (node (ref "VT3") (pin "3") (pinfunction "G2_3") (pintype "passive"))
      (node (ref "VT3") (pin "4") (pinfunction "G1_4") (pintype "passive"))
    )
    (net (code "52") (name "VCC1P8_LMS") (class "Default")
      (node (ref "C4") (pin "2") (pinfunction "2_2") (pintype "passive"))
      (node (ref "C5") (pin "2") (pinfunction "2_2") (pintype "passive"))
      (node (ref "C7") (pin "2") (pinfunction "2_2") (pintype "passive"))
      (node (ref "C8") (pin "2") (pinfunction "2_2") (pintype "passive"))
      (node (ref "MN1") (pin "2") (pinfunction "2_2") (pintype "passive"))
      (node (ref "MN10") (pin "2") (pinfunction "2_2") (pintype "passive"))
      (node (ref "MN2") (pin "2") (pinfunction "2_2") (pintype "passive"))
      (node (ref "MN9") (pin "2") (pinfunction "2_2") (pintype "passive"))
      (node (ref "R15") (pin "2") (pinfunction "2_2") (pintype "passive"))
    )
  )
)
